# controllers.net
KiCad netlist of a schematic drawn in Altium Designer
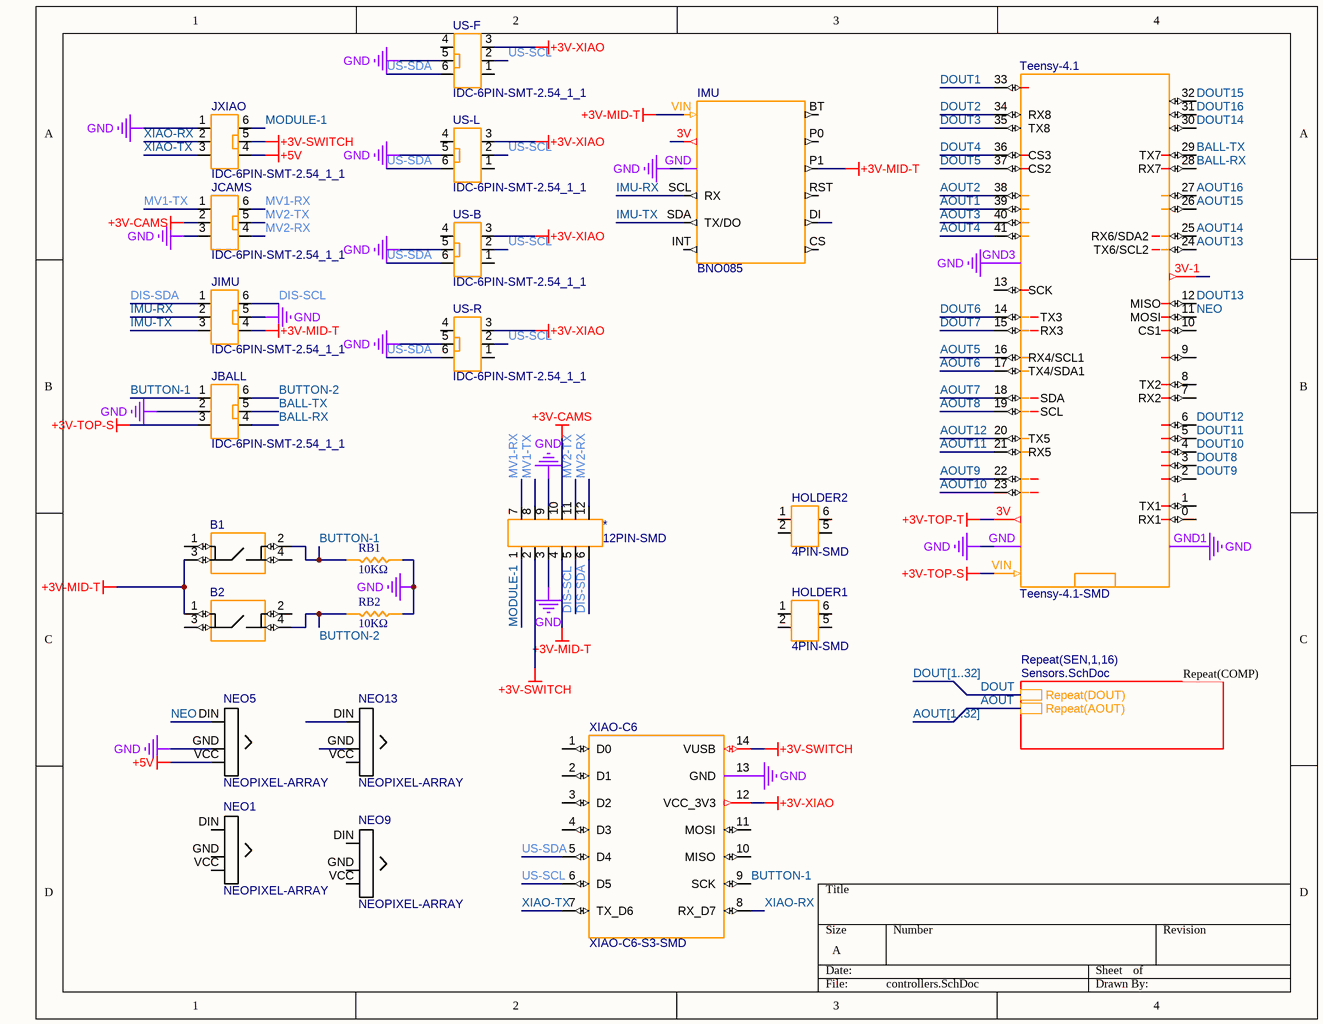
[diagram p0: controllers.SchDoc]

(export (version "E")
  (design (tool "Eeschema 10.0.6"))
  (components
    (comp (ref "*") (value "12PIN-SMD") (footprint "12PIN-SMD") (libsource (lib "RC") (part "12PIN-SMD")))
    (comp (ref "B1") (value "BUTTON") (footprint "BUTTON") (libsource (lib "RC") (part "BUTTON")))
    (comp (ref "B2") (value "BUTTON") (footprint "BUTTON") (libsource (lib "RC") (part "BUTTON")))
    (comp (ref "HOLDER1") (value "4PIN-SMD") (footprint "4PIN-SMD") (libsource (lib "RC") (part "4PIN-SMD")))
    (comp (ref "HOLDER2") (value "4PIN-SMD") (footprint "4PIN-SMD") (libsource (lib "RC") (part "4PIN-SMD")))
    (comp (ref "IMU") (value "BNO085") (footprint "BNO085") (libsource (lib "RC") (part "BNO085")))
    (comp (ref "JBALL")
      (value "IDC-6PIN-SMT-2.54_1_1")
      (footprint "IDC-6PIN-SMT-2.54")
      (libsource (lib "") (part "IDC-6PIN-SMT-2.54_1_1_1"))
    )
    (comp (ref "JCAMS")
      (value "IDC-6PIN-SMT-2.54_1_1")
      (footprint "IDC-6PIN-SMT-2.54")
      (libsource (lib "") (part "IDC-6PIN-SMT-2.54_1_1_1"))
    )
    (comp (ref "JIMU")
      (value "IDC-6PIN-SMT-2.54_1_1")
      (footprint "IDC-6PIN-SMT-2.54")
      (libsource (lib "") (part "IDC-6PIN-SMT-2.54_1_1_1"))
    )
    (comp (ref "JXIAO")
      (value "IDC-6PIN-SMT-2.54_1_1")
      (footprint "IDC-6PIN-SMT-2.54")
      (libsource (lib "") (part "IDC-6PIN-SMT-2.54_1_1_1"))
    )
    (comp (ref "NEO1")
      (value "NEOPIXEL-ARRAY")
      (footprint "NEOPIXEL-ARRAY")
      (libsource (lib "RC") (part "NEOPIXEL-ARRAY"))
    )
    (comp (ref "NEO5")
      (value "NEOPIXEL-ARRAY")
      (footprint "NEOPIXEL-ARRAY")
      (libsource (lib "RC") (part "NEOPIXEL-ARRAY"))
    )
    (comp (ref "NEO9")
      (value "NEOPIXEL-ARRAY")
      (footprint "NEOPIXEL-ARRAY")
      (libsource (lib "RC") (part "NEOPIXEL-ARRAY"))
    )
    (comp (ref "NEO13")
      (value "NEOPIXEL-ARRAY")
      (footprint "NEOPIXEL-ARRAY")
      (libsource (lib "RC") (part "NEOPIXEL-ARRAY"))
    )
    (comp (ref "RB1")
      (value "10KΩ")
      (footprint "RES_0603")
      (description "Resistor SMD 0603 generic")
      (libsource (lib "RC") (part "RES_0603"))
    )
    (comp (ref "RB2")
      (value "10KΩ")
      (footprint "RES_0603")
      (description "Resistor SMD 0603 generic")
      (libsource (lib "RC") (part "RES_0603"))
    )
    (comp (ref "Teensy-4.1")
      (value "Teensy-4.1-SMD")
      (footprint "TEENSY-4.1-SMD")
      (libsource (lib "RC") (part "Teensy-4.1-SMD"))
    )
    (comp (ref "US-B")
      (value "IDC-6PIN-SMT-2.54_1_1")
      (footprint "IDC-6PIN-SMT-2.54")
      (libsource (lib "RC") (part "IDC-6PIN-SMT-2.54_1_1"))
    )
    (comp (ref "US-F")
      (value "IDC-6PIN-SMT-2.54_1_1")
      (footprint "IDC-6PIN-SMT-2.54")
      (libsource (lib "RC") (part "IDC-6PIN-SMT-2.54_1_1"))
    )
    (comp (ref "US-L")
      (value "IDC-6PIN-SMT-2.54_1_1")
      (footprint "IDC-6PIN-SMT-2.54")
      (libsource (lib "RC") (part "IDC-6PIN-SMT-2.54_1_1"))
    )
    (comp (ref "US-R")
      (value "IDC-6PIN-SMT-2.54_1_1")
      (footprint "IDC-6PIN-SMT-2.54")
      (libsource (lib "RC") (part "IDC-6PIN-SMT-2.54_1_1"))
    )
    (comp (ref "XIAO-C6")
      (value "XIAO-C6-S3-SMD")
      (footprint "XIAO-C6-S3-SMD")
      (libsource (lib "RC") (part "XIAO-C6-S3-SMD"))
    )
  )
  (nets
    (net (code "33") (name "+3V-CAMS") (class "Default")
      (node (ref "*") (pin "10") (pintype "passive"))
      (node (ref "JCAMS") (pin "2") (pintype "passive"))
    )
    (net (code "34") (name "+3V-MID-T") (class "Default")
      (node (ref "*") (pin "4") (pintype "passive"))
      (node (ref "B1") (pin "3") (pinfunction "3_3") (pintype "bidirectional"))
      (node (ref "B2") (pin "1") (pinfunction "1_1") (pintype "bidirectional"))
      (node (ref "IMU") (pin "P1") (pintype "output"))
      (node (ref "IMU") (pin "VIN") (pintype "input"))
      (node (ref "JIMU") (pin "4") (pintype "passive"))
    )
    (net (code "35") (name "+3V-SWITCH") (class "Default")
      (node (ref "*") (pin "2") (pintype "passive"))
      (node (ref "JXIAO") (pin "5") (pintype "passive"))
      (node (ref "XIAO-C6") (pin "14") (pinfunction "VUSB_14") (pintype "bidirectional"))
    )
    (net (code "36") (name "+3V-TOP-S") (class "Default")
      (node (ref "JBALL") (pin "3") (pintype "passive"))
      (node (ref "Teensy-4.1") (pin "VIN") (pintype "input"))
    )
    (net (code "37") (name "+3V-TOP-T") (class "Default")
      (node (ref "Teensy-4.1") (pin "3V") (pintype "output"))
    )
    (net (code "38") (name "+3V-XIAO") (class "Default")
      (node (ref "US-B") (pin "3") (pintype "passive"))
      (node (ref "US-F") (pin "3") (pintype "passive"))
      (node (ref "US-L") (pin "3") (pintype "passive"))
      (node (ref "US-R") (pin "3") (pintype "passive"))
      (node (ref "XIAO-C6") (pin "12") (pinfunction "VCC_3V3_12") (pintype "output"))
    )
    (net (code "39") (name "+5V") (class "Default")
      (node (ref "JXIAO") (pin "4") (pintype "passive"))
      (node (ref "NEO5") (pin "VCC") (pintype "passive"))
    )
    (net (code "41") (name "/AOUT1") (class "Default")
      (node (ref "Teensy-4.1") (pin "39") (pintype "bidirectional"))
    )
    (net (code "42") (name "/AOUT2") (class "Default")
      (node (ref "Teensy-4.1") (pin "38") (pintype "bidirectional"))
    )
    (net (code "43") (name "/AOUT3") (class "Default")
      (node (ref "Teensy-4.1") (pin "40") (pintype "bidirectional"))
    )
    (net (code "44") (name "/AOUT4") (class "Default")
      (node (ref "Teensy-4.1") (pin "41") (pintype "bidirectional"))
    )
    (net (code "45") (name "/AOUT5") (class "Default")
      (node (ref "Teensy-4.1") (pin "16") (pinfunction "RX4/SCL1_16") (pintype "bidirectional"))
    )
    (net (code "46") (name "/AOUT6") (class "Default")
      (node (ref "Teensy-4.1") (pin "17") (pinfunction "TX4/SDA1_17") (pintype "bidirectional"))
    )
    (net (code "47") (name "/AOUT7") (class "Default")
      (node (ref "Teensy-4.1") (pin "18") (pinfunction "SDA_18") (pintype "bidirectional"))
    )
    (net (code "48") (name "/AOUT8") (class "Default")
      (node (ref "Teensy-4.1") (pin "19") (pinfunction "SCL_19") (pintype "bidirectional"))
    )
    (net (code "49") (name "/AOUT9") (class "Default")
      (node (ref "Teensy-4.1") (pin "22") (pintype "bidirectional"))
    )
    (net (code "50") (name "/AOUT10") (class "Default")
      (node (ref "Teensy-4.1") (pin "23") (pintype "bidirectional"))
    )
    (net (code "51") (name "/AOUT11") (class "Default")
      (node (ref "Teensy-4.1") (pin "21") (pinfunction "RX5_21") (pintype "bidirectional"))
    )
    (net (code "52") (name "/AOUT12") (class "Default")
      (node (ref "Teensy-4.1") (pin "20") (pinfunction "TX5_20") (pintype "bidirectional"))
    )
    (net (code "53") (name "/AOUT13") (class "Default")
      (node (ref "Teensy-4.1") (pin "24") (pinfunction "TX6/SCL2_24") (pintype "bidirectional"))
    )
    (net (code "54") (name "/AOUT14") (class "Default")
      (node (ref "Teensy-4.1") (pin "25") (pinfunction "RX6/SDA2_25") (pintype "bidirectional"))
    )
    (net (code "55") (name "/AOUT15") (class "Default")
      (node (ref "Teensy-4.1") (pin "26") (pintype "bidirectional"))
    )
    (net (code "56") (name "/AOUT16") (class "Default")
      (node (ref "Teensy-4.1") (pin "27") (pintype "bidirectional"))
    )
    (net (code "58") (name "/BALL-RX") (class "Default")
      (node (ref "JBALL") (pin "4") (pintype "passive"))
      (node (ref "Teensy-4.1") (pin "28") (pinfunction "RX7_28") (pintype "bidirectional"))
    )
    (net (code "59") (name "/BALL-TX") (class "Default")
      (node (ref "JBALL") (pin "5") (pintype "passive"))
      (node (ref "Teensy-4.1") (pin "29") (pinfunction "TX7_29") (pintype "bidirectional"))
    )
    (net (code "60") (name "/BUTTON-1") (class "Default")
      (node (ref "B1") (pin "2") (pinfunction "2_2") (pintype "bidirectional"))
      (node (ref "JBALL") (pin "1") (pintype "passive"))
      (node (ref "RB1") (pin "1") (pintype "passive"))
      (node (ref "XIAO-C6") (pin "9") (pinfunction "SCK_9") (pintype "bidirectional"))
    )
    (net (code "61") (name "/BUTTON-2") (class "Default")
      (node (ref "B2") (pin "4") (pinfunction "4_4") (pintype "bidirectional"))
      (node (ref "JBALL") (pin "6") (pintype "passive"))
      (node (ref "RB2") (pin "1") (pintype "passive"))
    )
    (net (code "62") (name "/DIS-SCL") (class "Default")
      (node (ref "*") (pin "5") (pintype "passive"))
      (node (ref "JIMU") (pin "6") (pintype "passive"))
    )
    (net (code "63") (name "/DIS-SDA") (class "Default")
      (node (ref "*") (pin "6") (pintype "passive"))
      (node (ref "JIMU") (pin "1") (pintype "passive"))
    )
    (net (code "65") (name "/DOUT1") (class "Default")
      (node (ref "Teensy-4.1") (pin "33") (pintype "bidirectional"))
    )
    (net (code "66") (name "/DOUT2") (class "Default")
      (node (ref "Teensy-4.1") (pin "34") (pinfunction "RX8_34") (pintype "bidirectional"))
    )
    (net (code "67") (name "/DOUT3") (class "Default")
      (node (ref "Teensy-4.1") (pin "35") (pinfunction "TX8_35") (pintype "bidirectional"))
    )
    (net (code "68") (name "/DOUT4") (class "Default")
      (node (ref "Teensy-4.1") (pin "36") (pinfunction "CS3_36") (pintype "bidirectional"))
    )
    (net (code "69") (name "/DOUT5") (class "Default")
      (node (ref "Teensy-4.1") (pin "37") (pinfunction "CS2_37") (pintype "bidirectional"))
    )
    (net (code "70") (name "/DOUT6") (class "Default")
      (node (ref "Teensy-4.1") (pin "14") (pinfunction "TX3_14") (pintype "bidirectional"))
    )
    (net (code "71") (name "/DOUT7") (class "Default")
      (node (ref "Teensy-4.1") (pin "15") (pinfunction "RX3_15") (pintype "bidirectional"))
    )
    (net (code "72") (name "/DOUT8") (class "Default")
      (node (ref "Teensy-4.1") (pin "3") (pintype "bidirectional"))
    )
    (net (code "73") (name "/DOUT9") (class "Default")
      (node (ref "Teensy-4.1") (pin "2") (pintype "bidirectional"))
    )
    (net (code "74") (name "/DOUT10") (class "Default")
      (node (ref "Teensy-4.1") (pin "4") (pintype "bidirectional"))
    )
    (net (code "75") (name "/DOUT11") (class "Default")
      (node (ref "Teensy-4.1") (pin "5") (pintype "bidirectional"))
    )
    (net (code "76") (name "/DOUT12") (class "Default")
      (node (ref "Teensy-4.1") (pin "6") (pintype "bidirectional"))
    )
    (net (code "77") (name "/DOUT13") (class "Default")
      (node (ref "Teensy-4.1") (pin "12") (pinfunction "MISO_12") (pintype "bidirectional"))
    )
    (net (code "78") (name "/DOUT14") (class "Default")
      (node (ref "Teensy-4.1") (pin "30") (pintype "bidirectional"))
    )
    (net (code "79") (name "/DOUT15") (class "Default")
      (node (ref "Teensy-4.1") (pin "32") (pintype "bidirectional"))
    )
    (net (code "80") (name "/DOUT16") (class "Default")
      (node (ref "Teensy-4.1") (pin "31") (pintype "bidirectional"))
    )
    (net (code "82") (name "/IMU-RX") (class "Default")
      (node (ref "IMU") (pin "SCL") (pinfunction "RX_SCL") (pintype "output"))
      (node (ref "JIMU") (pin "2") (pintype "passive"))
    )
    (net (code "83") (name "/IMU-TX") (class "Default")
      (node (ref "IMU") (pin "SDA") (pinfunction "TX/DO_SDA") (pintype "output"))
      (node (ref "JIMU") (pin "3") (pintype "passive"))
    )
    (net (code "84") (name "/MODULE-1") (class "Default")
      (node (ref "*") (pin "1") (pintype "passive"))
      (node (ref "JXIAO") (pin "6") (pintype "passive"))
    )
    (net (code "85") (name "/MV1-RX") (class "Default")
      (node (ref "*") (pin "7") (pintype "passive"))
      (node (ref "JCAMS") (pin "6") (pintype "passive"))
    )
    (net (code "86") (name "/MV1-TX") (class "Default")
      (node (ref "*") (pin "8") (pintype "passive"))
      (node (ref "JCAMS") (pin "1") (pintype "passive"))
    )
    (net (code "87") (name "/MV2-RX") (class "Default")
      (node (ref "*") (pin "12") (pintype "passive"))
      (node (ref "JCAMS") (pin "4") (pintype "passive"))
    )
    (net (code "88") (name "/MV2-TX") (class "Default")
      (node (ref "*") (pin "11") (pintype "passive"))
      (node (ref "JCAMS") (pin "5") (pintype "passive"))
    )
    (net (code "89") (name "/NEO") (class "Default")
      (node (ref "NEO5") (pin "DIN") (pintype "passive"))
      (node (ref "Teensy-4.1") (pin "11") (pinfunction "MOSI_11") (pintype "bidirectional"))
    )
    (net (code "90") (name "/US-SCL") (class "Default")
      (node (ref "US-B") (pin "2") (pintype "passive"))
      (node (ref "US-F") (pin "2") (pintype "passive"))
      (node (ref "US-L") (pin "2") (pintype "passive"))
      (node (ref "US-R") (pin "2") (pintype "passive"))
      (node (ref "XIAO-C6") (pin "6") (pinfunction "D5_6") (pintype "bidirectional"))
    )
    (net (code "91") (name "/US-SDA") (class "Default")
      (node (ref "US-B") (pin "6") (pintype "passive"))
      (node (ref "US-F") (pin "6") (pintype "passive"))
      (node (ref "US-L") (pin "6") (pintype "passive"))
      (node (ref "US-R") (pin "6") (pintype "passive"))
      (node (ref "XIAO-C6") (pin "5") (pinfunction "D4_5") (pintype "bidirectional"))
    )
    (net (code "92") (name "/XIAO-RX") (class "Default")
      (node (ref "JXIAO") (pin "2") (pintype "passive"))
      (node (ref "XIAO-C6") (pin "8") (pinfunction "RX_D7_8") (pintype "bidirectional"))
    )
    (net (code "93") (name "/XIAO-TX") (class "Default")
      (node (ref "JXIAO") (pin "3") (pintype "passive"))
      (node (ref "XIAO-C6") (pin "7") (pinfunction "TX_D6_7") (pintype "bidirectional"))
    )
    (net (code "94") (name "GND") (class "Default")
      (node (ref "*") (pin "3") (pintype "passive"))
      (node (ref "*") (pin "9") (pintype "passive"))
      (node (ref "IMU") (pin "GND") (pintype "passive"))
      (node (ref "JBALL") (pin "2") (pintype "passive"))
      (node (ref "JCAMS") (pin "3") (pintype "passive"))
      (node (ref "JIMU") (pin "5") (pintype "passive"))
      (node (ref "JXIAO") (pin "1") (pintype "passive"))
      (node (ref "NEO5") (pin "GND") (pintype "passive"))
      (node (ref "RB1") (pin "2") (pintype "passive"))
      (node (ref "RB2") (pin "2") (pintype "passive"))
      (node (ref "Teensy-4.1") (pin "GND") (pintype "passive"))
      (node (ref "Teensy-4.1") (pin "GND1") (pintype "passive"))
      (node (ref "Teensy-4.1") (pin "GND3") (pintype "power_in"))
      (node (ref "US-B") (pin "5") (pintype "passive"))
      (node (ref "US-F") (pin "5") (pintype "passive"))
      (node (ref "US-L") (pin "5") (pintype "passive"))
      (node (ref "US-R") (pin "5") (pintype "passive"))
      (node (ref "XIAO-C6") (pin "13") (pinfunction "GND_13") (pintype "power_in"))
    )
    (net (code "95") (name "unconnected-(B1-Pad1)") (class "Default")
      (node (ref "B1") (pin "1") (pinfunction "1_1") (pintype "bidirectional"))
    )
    (net (code "96") (name "unconnected-(B1-Pad4)") (class "Default")
      (node (ref "B1") (pin "4") (pinfunction "4_4") (pintype "bidirectional"))
    )
    (net (code "97") (name "unconnected-(B2-Pad2)") (class "Default")
      (node (ref "B2") (pin "2") (pinfunction "2_2") (pintype "bidirectional"))
    )
    (net (code "98") (name "unconnected-(B2-Pad3)") (class "Default")
      (node (ref "B2") (pin "3") (pinfunction "3_3") (pintype "bidirectional"))
    )
    (net (code "99") (name "unconnected-(HOLDER1-Pad1)") (class "Default")
      (node (ref "HOLDER1") (pin "1") (pintype "passive"))
    )
    (net (code "100") (name "unconnected-(HOLDER1-Pad2)") (class "Default")
      (node (ref "HOLDER1") (pin "2") (pintype "passive"))
    )
    (net (code "101") (name "unconnected-(HOLDER1-Pad5)") (class "Default")
      (node (ref "HOLDER1") (pin "5") (pintype "passive"))
    )
    (net (code "102") (name "unconnected-(HOLDER1-Pad6)") (class "Default")
      (node (ref "HOLDER1") (pin "6") (pintype "passive"))
    )
    (net (code "103") (name "unconnected-(HOLDER2-Pad1)") (class "Default")
      (node (ref "HOLDER2") (pin "1") (pintype "passive"))
    )
    (net (code "104") (name "unconnected-(HOLDER2-Pad2)") (class "Default")
      (node (ref "HOLDER2") (pin "2") (pintype "passive"))
    )
    (net (code "105") (name "unconnected-(HOLDER2-Pad5)") (class "Default")
      (node (ref "HOLDER2") (pin "5") (pintype "passive"))
    )
    (net (code "106") (name "unconnected-(HOLDER2-Pad6)") (class "Default")
      (node (ref "HOLDER2") (pin "6") (pintype "passive"))
    )
    (net (code "107") (name "unconnected-(IMU-Pad3V)") (class "Default")
      (node (ref "IMU") (pin "3V") (pintype "output"))
    )
    (net (code "108") (name "unconnected-(IMU-PadBT)") (class "Default")
      (node (ref "IMU") (pin "BT") (pintype "output"))
    )
    (net (code "109") (name "unconnected-(IMU-PadCS)") (class "Default")
      (node (ref "IMU") (pin "CS") (pintype "output"))
    )
    (net (code "110") (name "unconnected-(IMU-PadDI)") (class "Default")
      (node (ref "IMU") (pin "DI") (pintype "output"))
    )
    (net (code "111") (name "unconnected-(IMU-PadINT)") (class "Default")
      (node (ref "IMU") (pin "INT") (pintype "output"))
    )
    (net (code "112") (name "unconnected-(IMU-PadP0)") (class "Default")
      (node (ref "IMU") (pin "P0") (pintype "output"))
    )
    (net (code "113") (name "unconnected-(IMU-PadRST)") (class "Default")
      (node (ref "IMU") (pin "RST") (pintype "output"))
    )
    (net (code "114") (name "unconnected-(NEO1-PadDIN)") (class "Default")
      (node (ref "NEO1") (pin "DIN") (pintype "passive"))
    )
    (net (code "115") (name "unconnected-(NEO1-PadGND)") (class "Default")
      (node (ref "NEO1") (pin "GND") (pintype "passive"))
    )
    (net (code "116") (name "unconnected-(NEO1-PadVCC)") (class "Default")
      (node (ref "NEO1") (pin "VCC") (pintype "passive"))
    )
    (net (code "117") (name "unconnected-(NEO9-PadDIN)") (class "Default")
      (node (ref "NEO9") (pin "DIN") (pintype "passive"))
    )
    (net (code "118") (name "unconnected-(NEO9-PadGND)") (class "Default")
      (node (ref "NEO9") (pin "GND") (pintype "passive"))
    )
    (net (code "119") (name "unconnected-(NEO9-PadVCC)") (class "Default")
      (node (ref "NEO9") (pin "VCC") (pintype "passive"))
    )
    (net (code "120") (name "unconnected-(NEO13-PadDIN)") (class "Default")
      (node (ref "NEO13") (pin "DIN") (pintype "passive"))
    )
    (net (code "121") (name "unconnected-(NEO13-PadGND)") (class "Default")
      (node (ref "NEO13") (pin "GND") (pintype "passive"))
    )
    (net (code "122") (name "unconnected-(NEO13-PadVCC)") (class "Default")
      (node (ref "NEO13") (pin "VCC") (pintype "passive"))
    )
    (net (code "123") (name "unconnected-(Teensy-4.1-CS1-Pad10)") (class "Default")
      (node (ref "Teensy-4.1") (pin "10") (pinfunction "CS1_10") (pintype "bidirectional"))
    )
    (net (code "124") (name "unconnected-(Teensy-4.1-Pad3V-1)") (class "Default")
      (node (ref "Teensy-4.1") (pin "3V-1") (pintype "output"))
    )
    (net (code "125") (name "unconnected-(Teensy-4.1-Pad9)") (class "Default")
      (node (ref "Teensy-4.1") (pin "9") (pintype "bidirectional"))
    )
    (net (code "126") (name "unconnected-(Teensy-4.1-RX1-Pad0)") (class "Default")
      (node (ref "Teensy-4.1") (pin "0") (pinfunction "RX1_0") (pintype "bidirectional"))
    )
    (net (code "127") (name "unconnected-(Teensy-4.1-RX2-Pad7)") (class "Default")
      (node (ref "Teensy-4.1") (pin "7") (pinfunction "RX2_7") (pintype "bidirectional"))
    )
    (net (code "128") (name "unconnected-(Teensy-4.1-SCK-Pad13)") (class "Default")
      (node (ref "Teensy-4.1") (pin "13") (pinfunction "SCK_13") (pintype "bidirectional"))
    )
    (net (code "129") (name "unconnected-(Teensy-4.1-TX1-Pad1)") (class "Default")
      (node (ref "Teensy-4.1") (pin "1") (pinfunction "TX1_1") (pintype "bidirectional"))
    )
    (net (code "130") (name "unconnected-(Teensy-4.1-TX2-Pad8)") (class "Default")
      (node (ref "Teensy-4.1") (pin "8") (pinfunction "TX2_8") (pintype "bidirectional"))
    )
    (net (code "131") (name "unconnected-(US-B-Pad1)") (class "Default")
      (node (ref "US-B") (pin "1") (pintype "passive"))
    )
    (net (code "132") (name "unconnected-(US-B-Pad4)") (class "Default")
      (node (ref "US-B") (pin "4") (pintype "passive"))
    )
    (net (code "133") (name "unconnected-(US-F-Pad1)") (class "Default")
      (node (ref "US-F") (pin "1") (pintype "passive"))
    )
    (net (code "134") (name "unconnected-(US-F-Pad4)") (class "Default")
      (node (ref "US-F") (pin "4") (pintype "passive"))
    )
    (net (code "135") (name "unconnected-(US-L-Pad1)") (class "Default")
      (node (ref "US-L") (pin "1") (pintype "passive"))
    )
    (net (code "136") (name "unconnected-(US-L-Pad4)") (class "Default")
      (node (ref "US-L") (pin "4") (pintype "passive"))
    )
    (net (code "137") (name "unconnected-(US-R-Pad1)") (class "Default")
      (node (ref "US-R") (pin "1") (pintype "passive"))
    )
    (net (code "138") (name "unconnected-(US-R-Pad4)") (class "Default")
      (node (ref "US-R") (pin "4") (pintype "passive"))
    )
    (net (code "139") (name "unconnected-(XIAO-C6-D0-Pad1)") (class "Default")
      (node (ref "XIAO-C6") (pin "1") (pinfunction "D0_1") (pintype "bidirectional"))
    )
    (net (code "140") (name "unconnected-(XIAO-C6-D1-Pad2)") (class "Default")
      (node (ref "XIAO-C6") (pin "2") (pinfunction "D1_2") (pintype "bidirectional"))
    )
    (net (code "141") (name "unconnected-(XIAO-C6-D2-Pad3)") (class "Default")
      (node (ref "XIAO-C6") (pin "3") (pinfunction "D2_3") (pintype "bidirectional"))
    )
    (net (code "142") (name "unconnected-(XIAO-C6-D3-Pad4)") (class "Default")
      (node (ref "XIAO-C6") (pin "4") (pinfunction "D3_4") (pintype "bidirectional"))
    )
    (net (code "143") (name "unconnected-(XIAO-C6-MISO-Pad10)") (class "Default")
      (node (ref "XIAO-C6") (pin "10") (pinfunction "MISO_10") (pintype "bidirectional"))
    )
    (net (code "144") (name "unconnected-(XIAO-C6-MOSI-Pad11)") (class "Default")
      (node (ref "XIAO-C6") (pin "11") (pinfunction "MOSI_11") (pintype "bidirectional"))
    )
  )
)
